# DBL_165_SerialIn_Register.net
KiCad netlist of a schematic drawn in Altium Designer
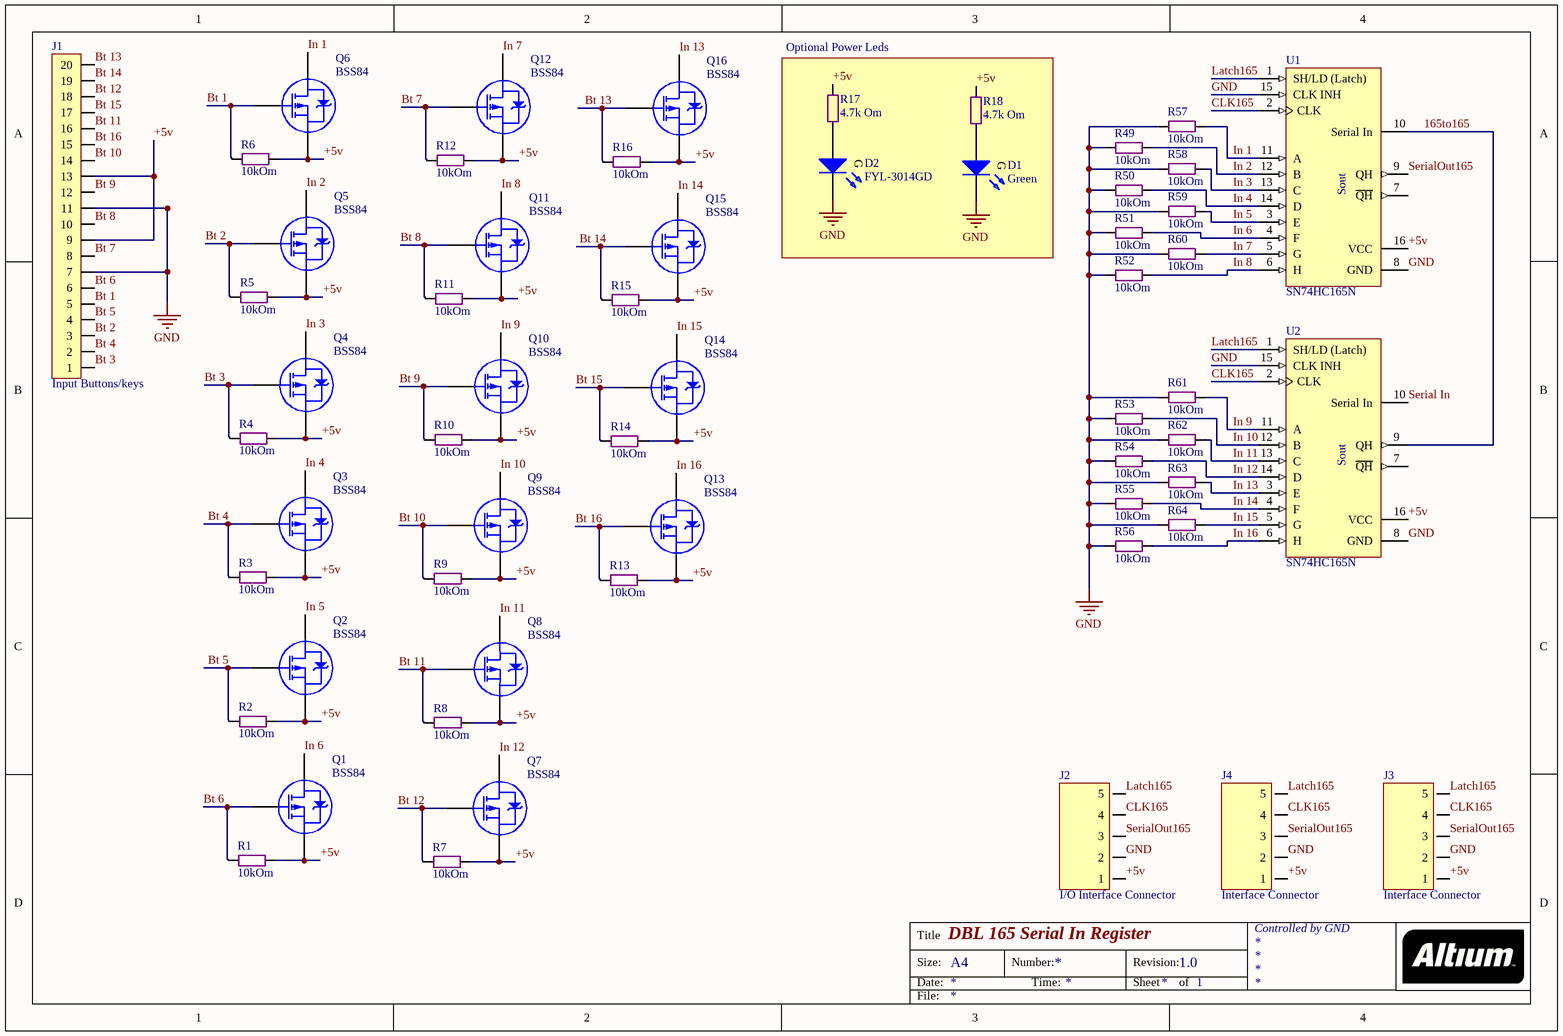
[diagram p0: DBL 165 SerialIn Register.SchDoc]

(export (version "E")
  (design (tool "Eeschema 10.0.6"))
  (components
    (comp (ref "D1")
      (value "Green")
      (footprint "LED:LED SMD 0805 Green")
      (description "?2v ?20mA")
      (libsource (lib "LED") (part "Led SMD Green"))
    )
    (comp (ref "D2")
      (value "FYL-3014GD")
      (footprint "LED:LED Round 3mm Green")
      (description "2.1v 10mA, 15-30mCd")
      (libsource (lib "LED") (part "Led Round 3mm Green"))
    )
    (comp (ref "J1")
      (value "Input Buttons/keys")
      (footprint "Connector:LINE 2.54 x 20D (2 x 10) - BH")
      (description "Vert, Dbl line, Male")
      (libsource (lib "Connector") (part "PLD-20 (2 x 10)"))
    )
    (comp (ref "J2")
      (value "I/O Interface Connector")
      (footprint "Connector:Line 2.54 x 5")
      (description "Vert, Sgl line, Male")
      (libsource (lib "Connector") (part "PLS-5"))
    )
    (comp (ref "J3")
      (value "Interface Connector")
      (footprint "Connector:Line 2.54 x 5")
      (description "Vert, Sgl line, Male")
      (libsource (lib "Connector") (part "PLS-5"))
    )
    (comp (ref "J4")
      (value "Interface Connector")
      (footprint "Connector:Line 2.54 x 5")
      (description "Vert, Sgl line, Male")
      (libsource (lib "Connector") (part "PLS-5"))
    )
    (comp (ref "Q1")
      (value "BSS84")
      (footprint "GeneralCases:SOT-23")
      (description "P-Channel -50V - 10-1Ω - 0.13A")
      (libsource (lib "Transistor") (part "BSS84"))
    )
    (comp (ref "Q2")
      (value "BSS84")
      (footprint "GeneralCases:SOT-23")
      (description "P-Channel -50V - 10-1Ω - 0.13A")
      (libsource (lib "Transistor") (part "BSS84"))
    )
    (comp (ref "Q3")
      (value "BSS84")
      (footprint "GeneralCases:SOT-23")
      (description "P-Channel -50V - 10-1Ω - 0.13A")
      (libsource (lib "Transistor") (part "BSS84"))
    )
    (comp (ref "Q4")
      (value "BSS84")
      (footprint "GeneralCases:SOT-23")
      (description "P-Channel -50V - 10-1Ω - 0.13A")
      (libsource (lib "Transistor") (part "BSS84"))
    )
    (comp (ref "Q5")
      (value "BSS84")
      (footprint "GeneralCases:SOT-23")
      (description "P-Channel -50V - 10-1Ω - 0.13A")
      (libsource (lib "Transistor") (part "BSS84"))
    )
    (comp (ref "Q6")
      (value "BSS84")
      (footprint "GeneralCases:SOT-23")
      (description "P-Channel -50V - 10-1Ω - 0.13A")
      (libsource (lib "Transistor") (part "BSS84"))
    )
    (comp (ref "Q7")
      (value "BSS84")
      (footprint "GeneralCases:SOT-23")
      (description "P-Channel -50V - 10-1Ω - 0.13A")
      (libsource (lib "Transistor") (part "BSS84"))
    )
    (comp (ref "Q8")
      (value "BSS84")
      (footprint "GeneralCases:SOT-23")
      (description "P-Channel -50V - 10-1Ω - 0.13A")
      (libsource (lib "Transistor") (part "BSS84"))
    )
    (comp (ref "Q9")
      (value "BSS84")
      (footprint "GeneralCases:SOT-23")
      (description "P-Channel -50V - 10-1Ω - 0.13A")
      (libsource (lib "Transistor") (part "BSS84"))
    )
    (comp (ref "Q10")
      (value "BSS84")
      (footprint "GeneralCases:SOT-23")
      (description "P-Channel -50V - 10-1Ω - 0.13A")
      (libsource (lib "Transistor") (part "BSS84"))
    )
    (comp (ref "Q11")
      (value "BSS84")
      (footprint "GeneralCases:SOT-23")
      (description "P-Channel -50V - 10-1Ω - 0.13A")
      (libsource (lib "Transistor") (part "BSS84"))
    )
    (comp (ref "Q12")
      (value "BSS84")
      (footprint "GeneralCases:SOT-23")
      (description "P-Channel -50V - 10-1Ω - 0.13A")
      (libsource (lib "Transistor") (part "BSS84"))
    )
    (comp (ref "Q13")
      (value "BSS84")
      (footprint "GeneralCases:SOT-23")
      (description "P-Channel -50V - 10-1Ω - 0.13A")
      (libsource (lib "Transistor") (part "BSS84"))
    )
    (comp (ref "Q14")
      (value "BSS84")
      (footprint "GeneralCases:SOT-23")
      (description "P-Channel -50V - 10-1Ω - 0.13A")
      (libsource (lib "Transistor") (part "BSS84"))
    )
    (comp (ref "Q15")
      (value "BSS84")
      (footprint "GeneralCases:SOT-23")
      (description "P-Channel -50V - 10-1Ω - 0.13A")
      (libsource (lib "Transistor") (part "BSS84"))
    )
    (comp (ref "Q16")
      (value "BSS84")
      (footprint "GeneralCases:SOT-23")
      (description "P-Channel -50V - 10-1Ω - 0.13A")
      (libsource (lib "Transistor") (part "BSS84"))
    )
    (comp (ref "R1")
      (value "10kOm")
      (footprint "PassiveComponents:SMD 0805 (2012)")
      (libsource (lib "PassiveComponents") (part "Res All Types"))
    )
    (comp (ref "R2")
      (value "10kOm")
      (footprint "PassiveComponents:SMD 0805 (2012)")
      (libsource (lib "PassiveComponents") (part "Res All Types"))
    )
    (comp (ref "R3")
      (value "10kOm")
      (footprint "PassiveComponents:SMD 0805 (2012)")
      (libsource (lib "PassiveComponents") (part "Res All Types"))
    )
    (comp (ref "R4")
      (value "10kOm")
      (footprint "PassiveComponents:SMD 0805 (2012)")
      (libsource (lib "PassiveComponents") (part "Res All Types"))
    )
    (comp (ref "R5")
      (value "10kOm")
      (footprint "PassiveComponents:SMD 0805 (2012)")
      (libsource (lib "PassiveComponents") (part "Res All Types"))
    )
    (comp (ref "R6")
      (value "10kOm")
      (footprint "PassiveComponents:SMD 0805 (2012)")
      (libsource (lib "PassiveComponents") (part "Res All Types"))
    )
    (comp (ref "R7")
      (value "10kOm")
      (footprint "PassiveComponents:SMD 0805 (2012)")
      (libsource (lib "PassiveComponents") (part "Res All Types"))
    )
    (comp (ref "R8")
      (value "10kOm")
      (footprint "PassiveComponents:SMD 0805 (2012)")
      (libsource (lib "PassiveComponents") (part "Res All Types"))
    )
    (comp (ref "R9")
      (value "10kOm")
      (footprint "PassiveComponents:SMD 0805 (2012)")
      (libsource (lib "PassiveComponents") (part "Res All Types"))
    )
    (comp (ref "R10")
      (value "10kOm")
      (footprint "PassiveComponents:SMD 0805 (2012)")
      (libsource (lib "PassiveComponents") (part "Res All Types"))
    )
    (comp (ref "R11")
      (value "10kOm")
      (footprint "PassiveComponents:SMD 0805 (2012)")
      (libsource (lib "PassiveComponents") (part "Res All Types"))
    )
    (comp (ref "R12")
      (value "10kOm")
      (footprint "PassiveComponents:SMD 0805 (2012)")
      (libsource (lib "PassiveComponents") (part "Res All Types"))
    )
    (comp (ref "R13")
      (value "10kOm")
      (footprint "PassiveComponents:SMD 0805 (2012)")
      (libsource (lib "PassiveComponents") (part "Res All Types"))
    )
    (comp (ref "R14")
      (value "10kOm")
      (footprint "PassiveComponents:SMD 0805 (2012)")
      (libsource (lib "PassiveComponents") (part "Res All Types"))
    )
    (comp (ref "R15")
      (value "10kOm")
      (footprint "PassiveComponents:SMD 0805 (2012)")
      (libsource (lib "PassiveComponents") (part "Res All Types"))
    )
    (comp (ref "R16")
      (value "10kOm")
      (footprint "PassiveComponents:SMD 0805 (2012)")
      (libsource (lib "PassiveComponents") (part "Res All Types"))
    )
    (comp (ref "R17")
      (value "4.7k Om")
      (footprint "PassiveComponents:SMD 0805 (2012)")
      (libsource (lib "PassiveComponents") (part "Res All Types"))
    )
    (comp (ref "R18")
      (value "4.7k Om")
      (footprint "PassiveComponents:SMD 0805 (2012)")
      (libsource (lib "PassiveComponents") (part "Res All Types"))
    )
    (comp (ref "R49")
      (value "10kOm")
      (footprint "PassiveComponents:SMD 0805 (2012)")
      (libsource (lib "PassiveComponents") (part "Res All Types"))
    )
    (comp (ref "R50")
      (value "10kOm")
      (footprint "PassiveComponents:SMD 0805 (2012)")
      (libsource (lib "PassiveComponents") (part "Res All Types"))
    )
    (comp (ref "R51")
      (value "10kOm")
      (footprint "PassiveComponents:SMD 0805 (2012)")
      (libsource (lib "PassiveComponents") (part "Res All Types"))
    )
    (comp (ref "R52")
      (value "10kOm")
      (footprint "PassiveComponents:SMD 0805 (2012)")
      (libsource (lib "PassiveComponents") (part "Res All Types"))
    )
    (comp (ref "R53")
      (value "10kOm")
      (footprint "PassiveComponents:SMD 0805 (2012)")
      (libsource (lib "PassiveComponents") (part "Res All Types"))
    )
    (comp (ref "R54")
      (value "10kOm")
      (footprint "PassiveComponents:SMD 0805 (2012)")
      (libsource (lib "PassiveComponents") (part "Res All Types"))
    )
    (comp (ref "R55")
      (value "10kOm")
      (footprint "PassiveComponents:SMD 0805 (2012)")
      (libsource (lib "PassiveComponents") (part "Res All Types"))
    )
    (comp (ref "R56")
      (value "10kOm")
      (footprint "PassiveComponents:SMD 0805 (2012)")
      (libsource (lib "PassiveComponents") (part "Res All Types"))
    )
    (comp (ref "R57")
      (value "10kOm")
      (footprint "PassiveComponents:SMD 0805 (2012)")
      (libsource (lib "PassiveComponents") (part "Res All Types"))
    )
    (comp (ref "R58")
      (value "10kOm")
      (footprint "PassiveComponents:SMD 0805 (2012)")
      (libsource (lib "PassiveComponents") (part "Res All Types"))
    )
    (comp (ref "R59")
      (value "10kOm")
      (footprint "PassiveComponents:SMD 0805 (2012)")
      (libsource (lib "PassiveComponents") (part "Res All Types"))
    )
    (comp (ref "R60")
      (value "10kOm")
      (footprint "PassiveComponents:SMD 0805 (2012)")
      (libsource (lib "PassiveComponents") (part "Res All Types"))
    )
    (comp (ref "R61")
      (value "10kOm")
      (footprint "PassiveComponents:SMD 0805 (2012)")
      (libsource (lib "PassiveComponents") (part "Res All Types"))
    )
    (comp (ref "R62")
      (value "10kOm")
      (footprint "PassiveComponents:SMD 0805 (2012)")
      (libsource (lib "PassiveComponents") (part "Res All Types"))
    )
    (comp (ref "R63")
      (value "10kOm")
      (footprint "PassiveComponents:SMD 0805 (2012)")
      (libsource (lib "PassiveComponents") (part "Res All Types"))
    )
    (comp (ref "R64")
      (value "10kOm")
      (footprint "PassiveComponents:SMD 0805 (2012)")
      (libsource (lib "PassiveComponents") (part "Res All Types"))
    )
    (comp (ref "U1")
      (value "SN74HC165N")
      (footprint "GeneralCases:DIP-16")
      (description "8-Bit Parallel-Load Shift Register")
      (fields (field (name "PUBLISHER") "Altium Limited"))
      (libsource (lib "Chips") (part "SN74HC165N"))
    )
    (comp (ref "U2")
      (value "SN74HC165N")
      (footprint "GeneralCases:DIP-16")
      (description "8-Bit Parallel-Load Shift Register")
      (fields (field (name "PUBLISHER") "Altium Limited"))
      (libsource (lib "Chips") (part "SN74HC165N"))
    )
  )
  (nets
    (net (code "1") (name "/+5v") (class "Default")
      (node (ref "J1") (pin "13") (pinfunction "13_13") (pintype "passive"))
      (node (ref "J1") (pin "9") (pinfunction "9_9") (pintype "passive"))
      (node (ref "J2") (pin "1") (pinfunction "1_1") (pintype "passive"))
      (node (ref "J3") (pin "1") (pinfunction "1_1") (pintype "passive"))
      (node (ref "J4") (pin "1") (pinfunction "1_1") (pintype "passive"))
      (node (ref "Q1") (pin "3") (pinfunction "S_3") (pintype "passive"))
      (node (ref "Q10") (pin "3") (pinfunction "S_3") (pintype "passive"))
      (node (ref "Q11") (pin "3") (pinfunction "S_3") (pintype "passive"))
      (node (ref "Q12") (pin "3") (pinfunction "S_3") (pintype "passive"))
      (node (ref "Q13") (pin "3") (pinfunction "S_3") (pintype "passive"))
      (node (ref "Q14") (pin "3") (pinfunction "S_3") (pintype "passive"))
      (node (ref "Q15") (pin "3") (pinfunction "S_3") (pintype "passive"))
      (node (ref "Q16") (pin "3") (pinfunction "S_3") (pintype "passive"))
      (node (ref "Q2") (pin "3") (pinfunction "S_3") (pintype "passive"))
      (node (ref "Q3") (pin "3") (pinfunction "S_3") (pintype "passive"))
      (node (ref "Q4") (pin "3") (pinfunction "S_3") (pintype "passive"))
      (node (ref "Q5") (pin "3") (pinfunction "S_3") (pintype "passive"))
      (node (ref "Q6") (pin "3") (pinfunction "S_3") (pintype "passive"))
      (node (ref "Q7") (pin "3") (pinfunction "S_3") (pintype "passive"))
      (node (ref "Q8") (pin "3") (pinfunction "S_3") (pintype "passive"))
      (node (ref "Q9") (pin "3") (pinfunction "S_3") (pintype "passive"))
      (node (ref "R1") (pin "1") (pinfunction "1_1") (pintype "passive"))
      (node (ref "R10") (pin "1") (pinfunction "1_1") (pintype "passive"))
      (node (ref "R11") (pin "1") (pinfunction "1_1") (pintype "passive"))
      (node (ref "R12") (pin "1") (pinfunction "1_1") (pintype "passive"))
      (node (ref "R13") (pin "1") (pinfunction "1_1") (pintype "passive"))
      (node (ref "R14") (pin "1") (pinfunction "1_1") (pintype "passive"))
      (node (ref "R15") (pin "1") (pinfunction "1_1") (pintype "passive"))
      (node (ref "R16") (pin "1") (pinfunction "1_1") (pintype "passive"))
      (node (ref "R17") (pin "1") (pinfunction "1_1") (pintype "passive"))
      (node (ref "R18") (pin "1") (pinfunction "1_1") (pintype "passive"))
      (node (ref "R2") (pin "1") (pinfunction "1_1") (pintype "passive"))
      (node (ref "R3") (pin "1") (pinfunction "1_1") (pintype "passive"))
      (node (ref "R4") (pin "1") (pinfunction "1_1") (pintype "passive"))
      (node (ref "R5") (pin "1") (pinfunction "1_1") (pintype "passive"))
      (node (ref "R6") (pin "1") (pinfunction "1_1") (pintype "passive"))
      (node (ref "R7") (pin "1") (pinfunction "1_1") (pintype "passive"))
      (node (ref "R8") (pin "1") (pinfunction "1_1") (pintype "passive"))
      (node (ref "R9") (pin "1") (pinfunction "1_1") (pintype "passive"))
      (node (ref "U1") (pin "16") (pinfunction "VCC_16") (pintype "power_in"))
      (node (ref "U2") (pin "16") (pinfunction "VCC_16") (pintype "power_in"))
    )
    (net (code "2") (name "/165to165") (class "Default")
      (node (ref "U1") (pin "10") (pinfunction "Serial_In_10") (pintype "passive"))
      (node (ref "U2") (pin "9") (pinfunction "QH_9") (pintype "output"))
    )
    (net (code "3") (name "/Bt 1") (class "Default")
      (node (ref "J1") (pin "5") (pinfunction "5_5") (pintype "passive"))
      (node (ref "Q6") (pin "1") (pinfunction "G_1") (pintype "passive"))
      (node (ref "R6") (pin "2") (pinfunction "2_2") (pintype "passive"))
    )
    (net (code "4") (name "/Bt 2") (class "Default")
      (node (ref "J1") (pin "3") (pinfunction "3_3") (pintype "passive"))
      (node (ref "Q5") (pin "1") (pinfunction "G_1") (pintype "passive"))
      (node (ref "R5") (pin "2") (pinfunction "2_2") (pintype "passive"))
    )
    (net (code "5") (name "/Bt 3") (class "Default")
      (node (ref "J1") (pin "1") (pinfunction "1_1") (pintype "passive"))
      (node (ref "Q4") (pin "1") (pinfunction "G_1") (pintype "passive"))
      (node (ref "R4") (pin "2") (pinfunction "2_2") (pintype "passive"))
    )
    (net (code "6") (name "/Bt 4") (class "Default")
      (node (ref "J1") (pin "2") (pinfunction "2_2") (pintype "passive"))
      (node (ref "Q3") (pin "1") (pinfunction "G_1") (pintype "passive"))
      (node (ref "R3") (pin "2") (pinfunction "2_2") (pintype "passive"))
    )
    (net (code "7") (name "/Bt 5") (class "Default")
      (node (ref "J1") (pin "4") (pinfunction "4_4") (pintype "passive"))
      (node (ref "Q2") (pin "1") (pinfunction "G_1") (pintype "passive"))
      (node (ref "R2") (pin "2") (pinfunction "2_2") (pintype "passive"))
    )
    (net (code "8") (name "/Bt 6") (class "Default")
      (node (ref "J1") (pin "6") (pinfunction "6_6") (pintype "passive"))
      (node (ref "Q1") (pin "1") (pinfunction "G_1") (pintype "passive"))
      (node (ref "R1") (pin "2") (pinfunction "2_2") (pintype "passive"))
    )
    (net (code "9") (name "/Bt 7") (class "Default")
      (node (ref "J1") (pin "8") (pinfunction "8_8") (pintype "passive"))
      (node (ref "Q12") (pin "1") (pinfunction "G_1") (pintype "passive"))
      (node (ref "R12") (pin "2") (pinfunction "2_2") (pintype "passive"))
    )
    (net (code "10") (name "/Bt 8") (class "Default")
      (node (ref "J1") (pin "10") (pinfunction "10_10") (pintype "passive"))
      (node (ref "Q11") (pin "1") (pinfunction "G_1") (pintype "passive"))
      (node (ref "R11") (pin "2") (pinfunction "2_2") (pintype "passive"))
    )
    (net (code "11") (name "/Bt 9") (class "Default")
      (node (ref "J1") (pin "12") (pinfunction "12_12") (pintype "passive"))
      (node (ref "Q10") (pin "1") (pinfunction "G_1") (pintype "passive"))
      (node (ref "R10") (pin "2") (pinfunction "2_2") (pintype "passive"))
    )
    (net (code "12") (name "/Bt 10") (class "Default")
      (node (ref "J1") (pin "14") (pinfunction "14_14") (pintype "passive"))
      (node (ref "Q9") (pin "1") (pinfunction "G_1") (pintype "passive"))
      (node (ref "R9") (pin "2") (pinfunction "2_2") (pintype "passive"))
    )
    (net (code "13") (name "/Bt 11") (class "Default")
      (node (ref "J1") (pin "16") (pinfunction "16_16") (pintype "passive"))
      (node (ref "Q8") (pin "1") (pinfunction "G_1") (pintype "passive"))
      (node (ref "R8") (pin "2") (pinfunction "2_2") (pintype "passive"))
    )
    (net (code "14") (name "/Bt 12") (class "Default")
      (node (ref "J1") (pin "18") (pinfunction "18_18") (pintype "passive"))
      (node (ref "Q7") (pin "1") (pinfunction "G_1") (pintype "passive"))
      (node (ref "R7") (pin "2") (pinfunction "2_2") (pintype "passive"))
    )
    (net (code "15") (name "/Bt 13") (class "Default")
      (node (ref "J1") (pin "20") (pinfunction "20_20") (pintype "passive"))
      (node (ref "Q16") (pin "1") (pinfunction "G_1") (pintype "passive"))
      (node (ref "R16") (pin "2") (pinfunction "2_2") (pintype "passive"))
    )
    (net (code "16") (name "/Bt 14") (class "Default")
      (node (ref "J1") (pin "19") (pinfunction "19_19") (pintype "passive"))
      (node (ref "Q15") (pin "1") (pinfunction "G_1") (pintype "passive"))
      (node (ref "R15") (pin "2") (pinfunction "2_2") (pintype "passive"))
    )
    (net (code "17") (name "/Bt 15") (class "Default")
      (node (ref "J1") (pin "17") (pinfunction "17_17") (pintype "passive"))
      (node (ref "Q14") (pin "1") (pinfunction "G_1") (pintype "passive"))
      (node (ref "R14") (pin "2") (pinfunction "2_2") (pintype "passive"))
    )
    (net (code "18") (name "/Bt 16") (class "Default")
      (node (ref "J1") (pin "15") (pinfunction "15_15") (pintype "passive"))
      (node (ref "Q13") (pin "1") (pinfunction "G_1") (pintype "passive"))
      (node (ref "R13") (pin "2") (pinfunction "2_2") (pintype "passive"))
    )
    (net (code "19") (name "/CLK165") (class "Default")
      (node (ref "J2") (pin "4") (pinfunction "4_4") (pintype "passive"))
      (node (ref "J3") (pin "4") (pinfunction "4_4") (pintype "passive"))
      (node (ref "J4") (pin "4") (pinfunction "4_4") (pintype "passive"))
      (node (ref "U1") (pin "2") (pinfunction "CLK_2") (pintype "input"))
      (node (ref "U2") (pin "2") (pinfunction "CLK_2") (pintype "input"))
    )
    (net (code "20") (name "/In 1") (class "Default")
      (node (ref "Q6") (pin "2") (pinfunction "D_2") (pintype "passive"))
      (node (ref "R57") (pin "2") (pinfunction "2_2") (pintype "passive"))
      (node (ref "U1") (pin "11") (pinfunction "A_11") (pintype "input"))
    )
    (net (code "21") (name "/In 2") (class "Default")
      (node (ref "Q5") (pin "2") (pinfunction "D_2") (pintype "passive"))
      (node (ref "R49") (pin "2") (pinfunction "2_2") (pintype "passive"))
      (node (ref "U1") (pin "12") (pinfunction "B_12") (pintype "input"))
    )
    (net (code "22") (name "/In 3") (class "Default")
      (node (ref "Q4") (pin "2") (pinfunction "D_2") (pintype "passive"))
      (node (ref "R58") (pin "2") (pinfunction "2_2") (pintype "passive"))
      (node (ref "U1") (pin "13") (pinfunction "C_13") (pintype "input"))
    )
    (net (code "23") (name "/In 4") (class "Default")
      (node (ref "Q3") (pin "2") (pinfunction "D_2") (pintype "passive"))
      (node (ref "R50") (pin "2") (pinfunction "2_2") (pintype "passive"))
      (node (ref "U1") (pin "14") (pinfunction "D_14") (pintype "input"))
    )
    (net (code "24") (name "/In 5") (class "Default")
      (node (ref "Q2") (pin "2") (pinfunction "D_2") (pintype "passive"))
      (node (ref "R59") (pin "2") (pinfunction "2_2") (pintype "passive"))
      (node (ref "U1") (pin "3") (pinfunction "E_3") (pintype "input"))
    )
    (net (code "25") (name "/In 6") (class "Default")
      (node (ref "Q1") (pin "2") (pinfunction "D_2") (pintype "passive"))
      (node (ref "R51") (pin "2") (pinfunction "2_2") (pintype "passive"))
      (node (ref "U1") (pin "4") (pinfunction "F_4") (pintype "input"))
    )
    (net (code "26") (name "/In 7") (class "Default")
      (node (ref "Q12") (pin "2") (pinfunction "D_2") (pintype "passive"))
      (node (ref "R60") (pin "2") (pinfunction "2_2") (pintype "passive"))
      (node (ref "U1") (pin "5") (pinfunction "G_5") (pintype "input"))
    )
    (net (code "27") (name "/In 8") (class "Default")
      (node (ref "Q11") (pin "2") (pinfunction "D_2") (pintype "passive"))
      (node (ref "R52") (pin "2") (pinfunction "2_2") (pintype "passive"))
      (node (ref "U1") (pin "6") (pinfunction "H_6") (pintype "input"))
    )
    (net (code "28") (name "/In 9") (class "Default")
      (node (ref "Q10") (pin "2") (pinfunction "D_2") (pintype "passive"))
      (node (ref "R61") (pin "2") (pinfunction "2_2") (pintype "passive"))
      (node (ref "U2") (pin "11") (pinfunction "A_11") (pintype "input"))
    )
    (net (code "29") (name "/In 10") (class "Default")
      (node (ref "Q9") (pin "2") (pinfunction "D_2") (pintype "passive"))
      (node (ref "R53") (pin "2") (pinfunction "2_2") (pintype "passive"))
      (node (ref "U2") (pin "12") (pinfunction "B_12") (pintype "input"))
    )
    (net (code "30") (name "/In 11") (class "Default")
      (node (ref "Q8") (pin "2") (pinfunction "D_2") (pintype "passive"))
      (node (ref "R62") (pin "2") (pinfunction "2_2") (pintype "passive"))
      (node (ref "U2") (pin "13") (pinfunction "C_13") (pintype "input"))
    )
    (net (code "31") (name "/In 12") (class "Default")
      (node (ref "Q7") (pin "2") (pinfunction "D_2") (pintype "passive"))
      (node (ref "R54") (pin "2") (pinfunction "2_2") (pintype "passive"))
      (node (ref "U2") (pin "14") (pinfunction "D_14") (pintype "input"))
    )
    (net (code "32") (name "/In 13") (class "Default")
      (node (ref "Q16") (pin "2") (pinfunction "D_2") (pintype "passive"))
      (node (ref "R63") (pin "2") (pinfunction "2_2") (pintype "passive"))
      (node (ref "U2") (pin "3") (pinfunction "E_3") (pintype "input"))
    )
    (net (code "33") (name "/In 14") (class "Default")
      (node (ref "Q15") (pin "2") (pinfunction "D_2") (pintype "passive"))
      (node (ref "R55") (pin "2") (pinfunction "2_2") (pintype "passive"))
      (node (ref "U2") (pin "4") (pinfunction "F_4") (pintype "input"))
    )
    (net (code "34") (name "/In 15") (class "Default")
      (node (ref "Q14") (pin "2") (pinfunction "D_2") (pintype "passive"))
      (node (ref "R64") (pin "2") (pinfunction "2_2") (pintype "passive"))
      (node (ref "U2") (pin "5") (pinfunction "G_5") (pintype "input"))
    )
    (net (code "35") (name "/In 16") (class "Default")
      (node (ref "Q13") (pin "2") (pinfunction "D_2") (pintype "passive"))
      (node (ref "R56") (pin "2") (pinfunction "2_2") (pintype "passive"))
      (node (ref "U2") (pin "6") (pinfunction "H_6") (pintype "input"))
    )
    (net (code "36") (name "/Latch165") (class "Default")
      (node (ref "J2") (pin "5") (pinfunction "5_5") (pintype "passive"))
      (node (ref "J3") (pin "5") (pinfunction "5_5") (pintype "passive"))
      (node (ref "J4") (pin "5") (pinfunction "5_5") (pintype "passive"))
      (node (ref "U1") (pin "1") (pinfunction "SH/LD_(Latch)_1") (pintype "input"))
      (node (ref "U2") (pin "1") (pinfunction "SH/LD_(Latch)_1") (pintype "input"))
    )
    (net (code "37") (name "/Serial In") (class "Default")
      (node (ref "U2") (pin "10") (pinfunction "Serial_In_10") (pintype "passive"))
    )
    (net (code "38") (name "/SerialOut165") (class "Default")
      (node (ref "J2") (pin "3") (pinfunction "3_3") (pintype "passive"))
      (node (ref "J3") (pin "3") (pinfunction "3_3") (pintype "passive"))
      (node (ref "J4") (pin "3") (pinfunction "3_3") (pintype "passive"))
      (node (ref "U1") (pin "9") (pinfunction "QH_9") (pintype "output"))
    )
    (net (code "39") (name "GND") (class "Default")
      (node (ref "D1") (pin "K") (pinfunction "K_K") (pintype "passive"))
      (node (ref "D2") (pin "K") (pinfunction "K_K") (pintype "passive"))
      (node (ref "J1") (pin "11") (pinfunction "11_11") (pintype "passive"))
      (node (ref "J1") (pin "7") (pinfunction "7_7") (pintype "passive"))
      (node (ref "J2") (pin "2") (pinfunction "2_2") (pintype "passive"))
      (node (ref "J3") (pin "2") (pinfunction "2_2") (pintype "passive"))
      (node (ref "J4") (pin "2") (pinfunction "2_2") (pintype "passive"))
      (node (ref "R49") (pin "1") (pinfunction "1_1") (pintype "passive"))
      (node (ref "R50") (pin "1") (pinfunction "1_1") (pintype "passive"))
      (node (ref "R51") (pin "1") (pinfunction "1_1") (pintype "passive"))
      (node (ref "R52") (pin "1") (pinfunction "1_1") (pintype "passive"))
      (node (ref "R53") (pin "1") (pinfunction "1_1") (pintype "passive"))
      (node (ref "R54") (pin "1") (pinfunction "1_1") (pintype "passive"))
      (node (ref "R55") (pin "1") (pinfunction "1_1") (pintype "passive"))
      (node (ref "R56") (pin "1") (pinfunction "1_1") (pintype "passive"))
      (node (ref "R57") (pin "1") (pinfunction "1_1") (pintype "passive"))
      (node (ref "R58") (pin "1") (pinfunction "1_1") (pintype "passive"))
      (node (ref "R59") (pin "1") (pinfunction "1_1") (pintype "passive"))
      (node (ref "R60") (pin "1") (pinfunction "1_1") (pintype "passive"))
      (node (ref "R61") (pin "1") (pinfunction "1_1") (pintype "passive"))
      (node (ref "R62") (pin "1") (pinfunction "1_1") (pintype "passive"))
      (node (ref "R63") (pin "1") (pinfunction "1_1") (pintype "passive"))
      (node (ref "R64") (pin "1") (pinfunction "1_1") (pintype "passive"))
      (node (ref "U1") (pin "15") (pinfunction "CLK_INH_15") (pintype "input"))
      (node (ref "U1") (pin "8") (pinfunction "GND_8") (pintype "power_in"))
      (node (ref "U2") (pin "15") (pinfunction "CLK_INH_15") (pintype "input"))
      (node (ref "U2") (pin "8") (pinfunction "GND_8") (pintype "power_in"))
    )
    (net (code "40") (name "Net-(D1-PadA)") (class "Default")
      (node (ref "D1") (pin "A") (pinfunction "A_A") (pintype "passive"))
      (node (ref "R18") (pin "2") (pinfunction "2_2") (pintype "passive"))
    )
    (net (code "41") (name "Net-(D2-PadA)") (class "Default")
      (node (ref "D2") (pin "A") (pinfunction "A_A") (pintype "passive"))
      (node (ref "R17") (pin "2") (pinfunction "2_2") (pintype "passive"))
    )
    (net (code "42") (name "unconnected-(U1-~{QH}-Pad7)") (class "Default")
      (node (ref "U1") (pin "7") (pinfunction "~{QH}_7") (pintype "output"))
    )
    (net (code "43") (name "unconnected-(U2-~{QH}-Pad7)") (class "Default")
      (node (ref "U2") (pin "7") (pinfunction "~{QH}_7") (pintype "output"))
    )
  )
)
